# PowerBoost_500C.net
KiCad netlist of a schematic drawn in EAGLE
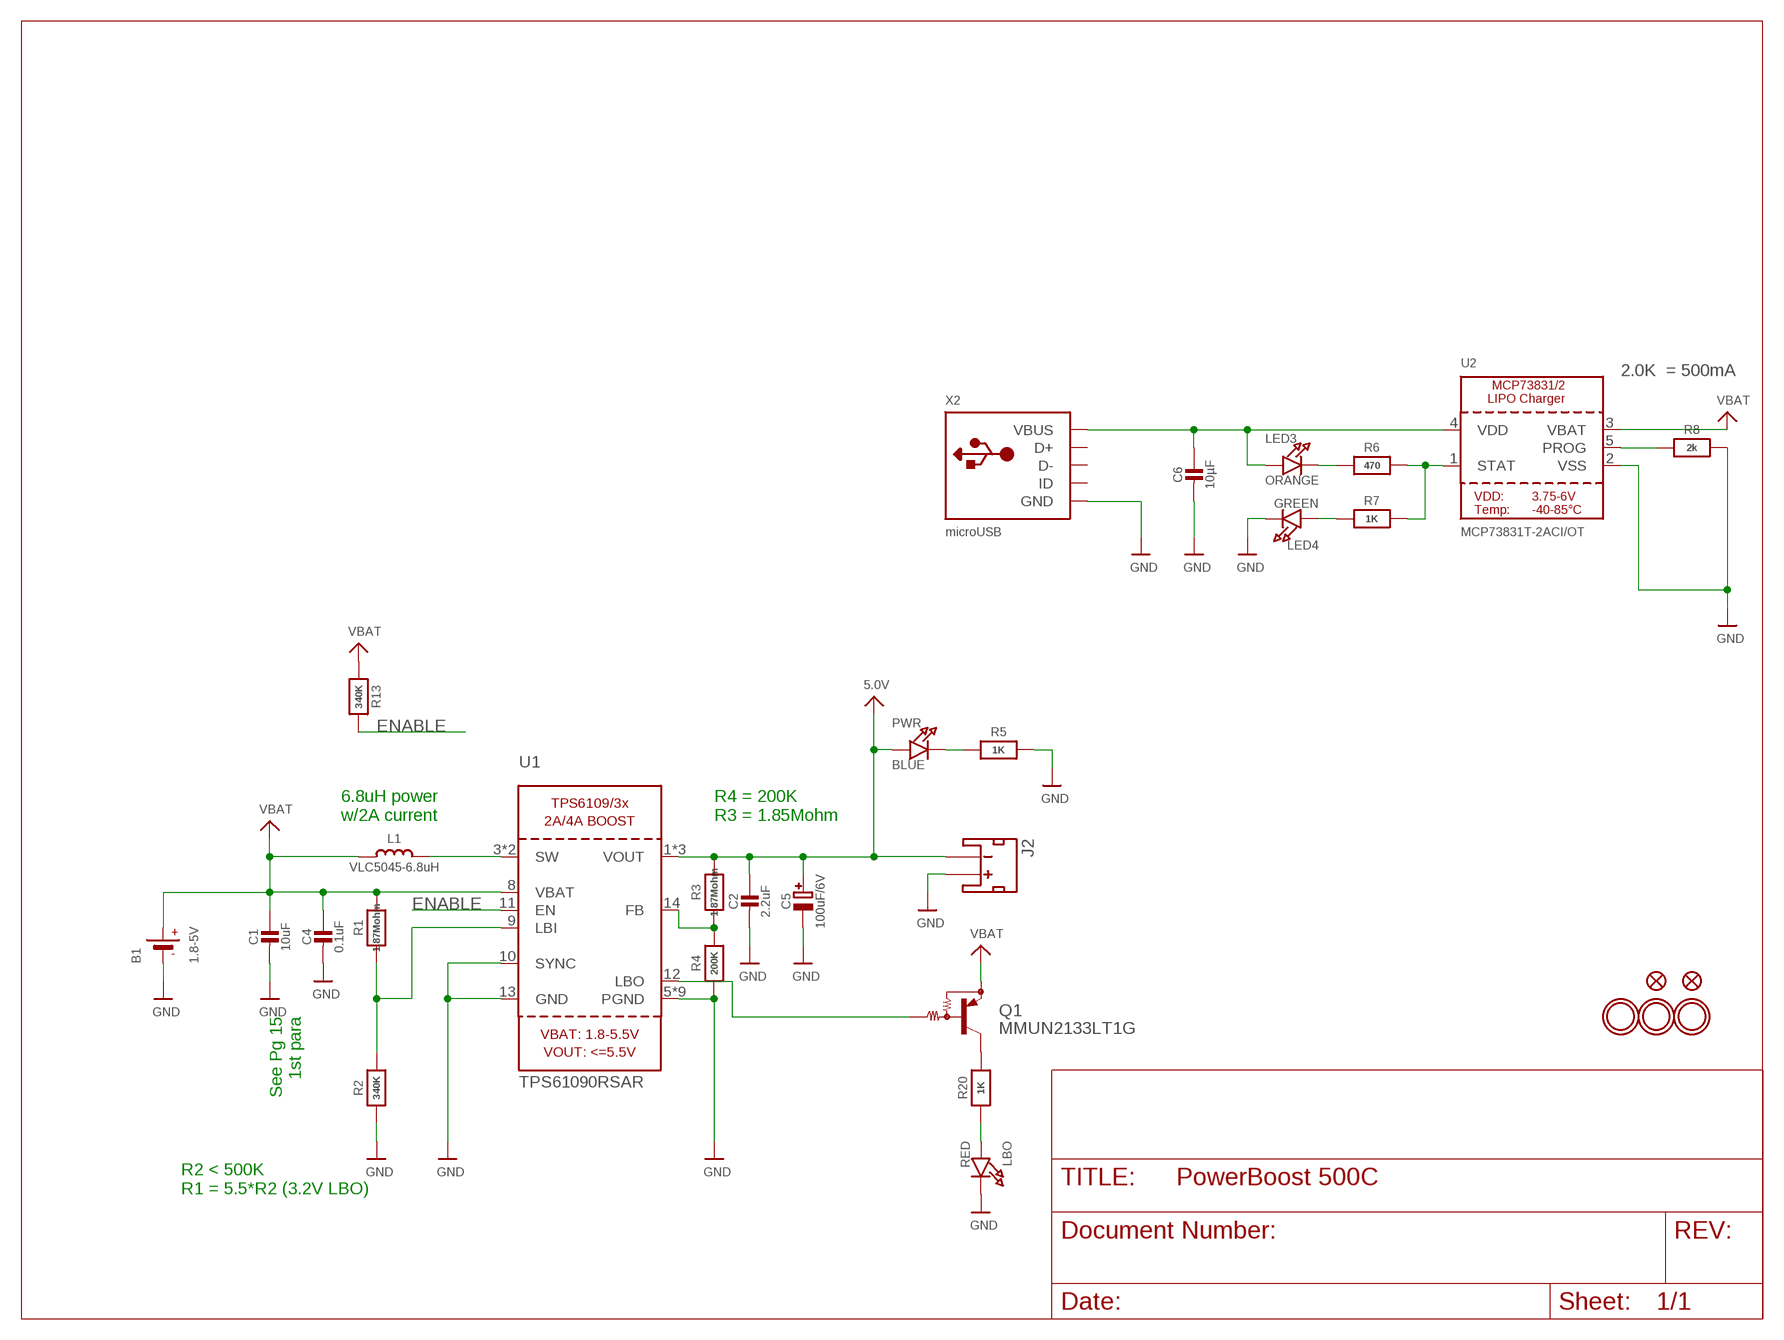
[diagram p0: schematic, sheet 1]

(export (version "E")
  (design (tool "Eeschema 10.0.6"))
  (components
    (comp (ref "B1")
      (value "1.8-5V")
      (footprint "eagle-import:JSTPH2")
      (libsource (lib "eagle-import") (part "BATTERY"))
    )
    (comp (ref "C1")
      (value "10uF")
      (footprint "eagle-import:0805-NO")
      (libsource (lib "eagle-import") (part "CAP_CERAMIC0805-NOOUTLINE"))
    )
    (comp (ref "C2")
      (value "2.2uF")
      (footprint "eagle-import:0805-NO")
      (libsource (lib "eagle-import") (part "CAP_CERAMIC0805-NOOUTLINE"))
    )
    (comp (ref "C4")
      (value "0.1uF")
      (footprint "eagle-import:0805-NO")
      (libsource (lib "eagle-import") (part "CAP_CERAMIC0805-NOOUTLINE"))
    )
    (comp (ref "C5")
      (value "100uF/6V")
      (footprint "eagle-import:EIA3528-21_B-R")
      (libsource (lib "eagle-import") (part "CAP_TANTALUMB/3528_REFLOW"))
    )
    (comp (ref "C6")
      (value "10µF")
      (footprint "eagle-import:0805-NO")
      (libsource (lib "eagle-import") (part "CAP_CERAMIC0805-NOOUTLINE"))
    )
    (comp (ref "FID2")
      (value "FIDUCIAL\"\"")
      (footprint "eagle-import:FIDUCIAL_1MM")
      (libsource (lib "eagle-import") (part "FIDUCIAL{dblquote}{dblquote}"))
    )
    (comp (ref "FID3")
      (value "FIDUCIAL\"\"")
      (footprint "eagle-import:FIDUCIAL_1MM")
      (fields (field (name "BOM") "EXCLUDE"))
      (libsource (lib "eagle-import") (part "FIDUCIAL{dblquote}{dblquote}"))
    )
    (comp (ref "J2")
      (value "JST_2MM_MALE")
      (footprint "eagle-import:JST-2-SMD")
      (libsource (lib "eagle-import") (part "JST_2MM_MALE"))
    )
    (comp (ref "L1")
      (value "VLC5045-6.8uH")
      (footprint "eagle-import:INDUCTOR_5X5MM_TDK_VLC5045")
      (libsource (lib "eagle-import") (part "INDUCTORTDK_VLC5045"))
    )
    (comp (ref "LBO")
      (value "RED")
      (footprint "eagle-import:CHIPLED_0805_NOOUTLINE")
      (libsource (lib "eagle-import") (part "LED0805_NOOUTLINE"))
    )
    (comp (ref "LED3")
      (value "ORANGE")
      (footprint "eagle-import:CHIPLED_0805_NOOUTLINE")
      (libsource (lib "eagle-import") (part "LED0805_NOOUTLINE"))
    )
    (comp (ref "LED4")
      (value "GREEN")
      (footprint "eagle-import:CHIPLED_0805_NOOUTLINE")
      (libsource (lib "eagle-import") (part "LED0805_NOOUTLINE"))
    )
    (comp (ref "PWR")
      (value "BLUE")
      (footprint "eagle-import:CHIPLED_0805_NOOUTLINE")
      (libsource (lib "eagle-import") (part "LED0805_NOOUTLINE"))
    )
    (comp (ref "Q1")
      (value "MMUN2133LT1G")
      (footprint "eagle-import:SC59-BEC")
      (libsource (lib "eagle-import") (part "-PNP_DRIVER-SC59-BECMUN2114T1"))
    )
    (comp (ref "R1")
      (value "1.87Mohm")
      (footprint "eagle-import:0805-NO")
      (libsource (lib "eagle-import") (part "RESISTOR0805_NOOUTLINE"))
    )
    (comp (ref "R2")
      (value "340K")
      (footprint "eagle-import:0805-NO")
      (libsource (lib "eagle-import") (part "RESISTOR0805_NOOUTLINE"))
    )
    (comp (ref "R3")
      (value "1.87Mohm")
      (footprint "eagle-import:0805-NO")
      (libsource (lib "eagle-import") (part "RESISTOR0805_NOOUTLINE"))
    )
    (comp (ref "R4")
      (value "200K")
      (footprint "eagle-import:0805-NO")
      (libsource (lib "eagle-import") (part "RESISTOR0805_NOOUTLINE"))
    )
    (comp (ref "R5")
      (value "1K")
      (footprint "eagle-import:0805-NO")
      (libsource (lib "eagle-import") (part "RESISTOR0805_NOOUTLINE"))
    )
    (comp (ref "R6")
      (value "470")
      (footprint "eagle-import:0805-NO")
      (libsource (lib "eagle-import") (part "RESISTOR0805_NOOUTLINE"))
    )
    (comp (ref "R7")
      (value "1K")
      (footprint "eagle-import:0805-NO")
      (libsource (lib "eagle-import") (part "RESISTOR0805_NOOUTLINE"))
    )
    (comp (ref "R8")
      (value "2k")
      (footprint "eagle-import:0805-NO")
      (libsource (lib "eagle-import") (part "RESISTOR0805_NOOUTLINE"))
    )
    (comp (ref "R13")
      (value "340K")
      (footprint "eagle-import:0805-NO")
      (libsource (lib "eagle-import") (part "RESISTOR0805_NOOUTLINE"))
    )
    (comp (ref "R20")
      (value "1K")
      (footprint "eagle-import:0805-NO")
      (libsource (lib "eagle-import") (part "RESISTOR0805_NOOUTLINE"))
    )
    (comp (ref "U$10")
      (value "MOUNTINGHOLE2.5")
      (footprint "eagle-import:MOUNTINGHOLE_2.5_PLATED")
      (libsource (lib "eagle-import") (part "MOUNTINGHOLE2.5"))
    )
    (comp (ref "U$12")
      (value "MOUNTINGHOLE2.5")
      (footprint "eagle-import:MOUNTINGHOLE_2.5_PLATED")
      (libsource (lib "eagle-import") (part "MOUNTINGHOLE2.5"))
    )
    (comp (ref "U$15")
      (value "MOUNTINGHOLE2.5")
      (footprint "eagle-import:MOUNTINGHOLE_2.5_PLATED")
      (libsource (lib "eagle-import") (part "MOUNTINGHOLE2.5"))
    )
    (comp (ref "U1")
      (value "TPS61090RSAR")
      (footprint "eagle-import:PVQFN-16")
      (libsource (lib "eagle-import") (part "VREG_TPS6103X"))
    )
    (comp (ref "U2")
      (value "MCP73831T-2ACI/OT")
      (footprint "eagle-import:SOT23-5")
      (libsource (lib "eagle-import") (part "MCP73831/2"))
    )
    (comp (ref "X2")
      (value "microUSB")
      (footprint "eagle-import:4UCONN_20329")
      (libsource (lib "eagle-import") (part "USBMICRO_20329"))
    )
  )
  (nets
    (net (code "1") (name "/ENABLE") (class "Default")
      (node (ref "R13") (pin "2") (pinfunction "2_2") (pintype "passive"))
      (node (ref "U1") (pin "11") (pinfunction "EN_11") (pintype "input"))
    )
    (net (code "2") (name "5.0V") (class "Default")
      (node (ref "C2") (pin "1") (pinfunction "1_1") (pintype "passive"))
      (node (ref "C5") (pin "+") (pinfunction "+_+") (pintype "passive"))
      (node (ref "J2") (pin "1") (pinfunction "-_1") (pintype "bidirectional"))
      (node (ref "PWR") (pin "A") (pinfunction "A_A") (pintype "passive"))
      (node (ref "R3") (pin "2") (pinfunction "2_2") (pintype "passive"))
      (node (ref "U1") (pin "1") (pinfunction "VOUT_1") (pintype "power_in"))
      (node (ref "U1") (pin "15") (pinfunction "VOUT_15") (pintype "power_in"))
      (node (ref "U1") (pin "16") (pinfunction "VOUT_16") (pintype "power_in"))
    )
    (net (code "3") (name "GND") (class "Default")
      (node (ref "B1") (pin "1") (pinfunction "-_1") (pintype "passive"))
      (node (ref "C1") (pin "2") (pinfunction "2_2") (pintype "passive"))
      (node (ref "C2") (pin "2") (pinfunction "2_2") (pintype "passive"))
      (node (ref "C4") (pin "2") (pinfunction "2_2") (pintype "passive"))
      (node (ref "C5") (pin "-") (pinfunction "-_-") (pintype "passive"))
      (node (ref "C6") (pin "2") (pinfunction "2_2") (pintype "passive"))
      (node (ref "J2") (pin "2") (pinfunction "+_2") (pintype "bidirectional"))
      (node (ref "LBO") (pin "C") (pinfunction "C_C") (pintype "passive"))
      (node (ref "LED4") (pin "C") (pinfunction "C_C") (pintype "passive"))
      (node (ref "R2") (pin "1") (pinfunction "1_1") (pintype "passive"))
      (node (ref "R4") (pin "1") (pinfunction "1_1") (pintype "passive"))
      (node (ref "R5") (pin "2") (pinfunction "2_2") (pintype "passive"))
      (node (ref "R8") (pin "2") (pinfunction "2_2") (pintype "passive"))
      (node (ref "U1") (pin "10") (pinfunction "SYNC_10") (pintype "input"))
      (node (ref "U1") (pin "13") (pinfunction "GND_13") (pintype "power_in"))
      (node (ref "U1") (pin "5") (pinfunction "PGND_5") (pintype "power_in"))
      (node (ref "U1") (pin "6") (pinfunction "PGND_6") (pintype "power_in"))
      (node (ref "U1") (pin "7") (pinfunction "PGND_7") (pintype "power_in"))
      (node (ref "U1") (pin "P$18") (pinfunction "PGND_P$18") (pintype "power_in"))
      (node (ref "U1") (pin "P$19") (pinfunction "PGND_P$19") (pintype "power_in"))
      (node (ref "U1") (pin "P$20") (pinfunction "PGND_P$20") (pintype "power_in"))
      (node (ref "U1") (pin "P$21") (pinfunction "PGND_P$21") (pintype "power_in"))
      (node (ref "U1") (pin "P$22") (pinfunction "PGND_P$22") (pintype "power_in"))
      (node (ref "U1") (pin "THERMAL") (pinfunction "PGND_THERMAL") (pintype "power_in"))
      (node (ref "U2") (pin "2") (pinfunction "VSS_2") (pintype "power_in"))
      (node (ref "X2") (pin "BASE@1") (pinfunction "GND_BASE@1") (pintype "power_in"))
      (node (ref "X2") (pin "BASE@2") (pinfunction "GND_BASE@2") (pintype "power_in"))
      (node (ref "X2") (pin "GND") (pinfunction "GND_GND") (pintype "power_in"))
      (node (ref "X2") (pin "SPRT@1") (pinfunction "GND_SPRT@1") (pintype "power_in"))
      (node (ref "X2") (pin "SPRT@2") (pinfunction "GND_SPRT@2") (pintype "power_in"))
      (node (ref "X2") (pin "SPRT@3") (pinfunction "GND_SPRT@3") (pintype "power_in"))
      (node (ref "X2") (pin "SPRT@4") (pinfunction "GND_SPRT@4") (pintype "power_in"))
    )
    (net (code "4") (name "Net-(L1-2)") (class "Default")
      (node (ref "L1") (pin "P$2") (pinfunction "2_P$2") (pintype "passive"))
      (node (ref "U1") (pin "3") (pinfunction "SW_3") (pintype "input"))
      (node (ref "U1") (pin "4") (pinfunction "SW_4") (pintype "input"))
    )
    (net (code "5") (name "Net-(LBO-PadA)") (class "Default")
      (node (ref "LBO") (pin "A") (pinfunction "A_A") (pintype "passive"))
      (node (ref "R20") (pin "1") (pinfunction "1_1") (pintype "passive"))
    )
    (net (code "6") (name "Net-(LED3-PadC)") (class "Default")
      (node (ref "LED3") (pin "C") (pinfunction "C_C") (pintype "passive"))
      (node (ref "R6") (pin "1") (pinfunction "1_1") (pintype "passive"))
    )
    (net (code "7") (name "Net-(LED4-PadA)") (class "Default")
      (node (ref "LED4") (pin "A") (pinfunction "A_A") (pintype "passive"))
      (node (ref "R7") (pin "1") (pinfunction "1_1") (pintype "passive"))
    )
    (net (code "8") (name "Net-(PWR-PadC)") (class "Default")
      (node (ref "PWR") (pin "C") (pinfunction "C_C") (pintype "passive"))
      (node (ref "R5") (pin "1") (pinfunction "1_1") (pintype "passive"))
    )
    (net (code "9") (name "Net-(Q1-PadC)") (class "Default")
      (node (ref "Q1") (pin "C") (pinfunction "C_C") (pintype "passive"))
      (node (ref "R20") (pin "2") (pinfunction "2_2") (pintype "passive"))
    )
    (net (code "10") (name "Net-(U1-FB)") (class "Default")
      (node (ref "R3") (pin "1") (pinfunction "1_1") (pintype "passive"))
      (node (ref "R4") (pin "2") (pinfunction "2_2") (pintype "passive"))
      (node (ref "U1") (pin "14") (pinfunction "FB_14") (pintype "input"))
    )
    (net (code "11") (name "Net-(U1-LBI)") (class "Default")
      (node (ref "R1") (pin "1") (pinfunction "1_1") (pintype "passive"))
      (node (ref "R2") (pin "2") (pinfunction "2_2") (pintype "passive"))
      (node (ref "U1") (pin "9") (pinfunction "LBI_9") (pintype "input"))
    )
    (net (code "12") (name "Net-(U1-LBO)") (class "Default")
      (node (ref "Q1") (pin "B") (pinfunction "B_B") (pintype "passive"))
      (node (ref "U1") (pin "12") (pinfunction "LBO_12") (pintype "output"))
    )
    (net (code "13") (name "Net-(U2-PROG)") (class "Default")
      (node (ref "R8") (pin "1") (pinfunction "1_1") (pintype "passive"))
      (node (ref "U2") (pin "5") (pinfunction "PROG_5") (pintype "input"))
    )
    (net (code "14") (name "Net-(U2-STAT)") (class "Default")
      (node (ref "R6") (pin "2") (pinfunction "2_2") (pintype "passive"))
      (node (ref "R7") (pin "2") (pinfunction "2_2") (pintype "passive"))
      (node (ref "U2") (pin "1") (pinfunction "STAT_1") (pintype "output"))
    )
    (net (code "15") (name "Net-(U2-VDD)") (class "Default")
      (node (ref "C6") (pin "1") (pinfunction "1_1") (pintype "passive"))
      (node (ref "LED3") (pin "A") (pinfunction "A_A") (pintype "passive"))
      (node (ref "U2") (pin "4") (pinfunction "VDD_4") (pintype "power_in"))
      (node (ref "X2") (pin "VBUS") (pinfunction "VBUS_VBUS") (pintype "power_in"))
    )
    (net (code "16") (name "VBAT") (class "Default")
      (node (ref "B1") (pin "2") (pinfunction "+_2") (pintype "passive"))
      (node (ref "C1") (pin "1") (pinfunction "1_1") (pintype "passive"))
      (node (ref "C4") (pin "1") (pinfunction "1_1") (pintype "passive"))
      (node (ref "L1") (pin "P$1") (pinfunction "1_P$1") (pintype "passive"))
      (node (ref "Q1") (pin "E") (pinfunction "E_E") (pintype "passive"))
      (node (ref "R1") (pin "2") (pinfunction "2_2") (pintype "passive"))
      (node (ref "R13") (pin "1") (pinfunction "1_1") (pintype "passive"))
      (node (ref "U1") (pin "8") (pinfunction "VBAT_8") (pintype "input"))
      (node (ref "U2") (pin "3") (pinfunction "VBAT_3") (pintype "power_in"))
    )
    (net (code "17") (name "unconnected-(J2-PAD1-PadNC1)") (class "Default")
      (node (ref "J2") (pin "NC1") (pinfunction "PAD1_NC1") (pintype "bidirectional"))
    )
    (net (code "18") (name "unconnected-(J2-PAD2-PadNC2)") (class "Default")
      (node (ref "J2") (pin "NC2") (pinfunction "PAD2_NC2") (pintype "bidirectional"))
    )
    (net (code "19") (name "unconnected-(X2-PadD+)") (class "Default")
      (node (ref "X2") (pin "D+") (pinfunction "D+_D+") (pintype "bidirectional"))
    )
    (net (code "20") (name "unconnected-(X2-PadD-)") (class "Default")
      (node (ref "X2") (pin "D-") (pinfunction "D-_D-") (pintype "bidirectional"))
    )
    (net (code "21") (name "unconnected-(X2-PadID)") (class "Default")
      (node (ref "X2") (pin "ID") (pinfunction "ID_ID") (pintype "bidirectional"))
    )
  )
)
